# PS_MIO.net
KiCad netlist of a schematic drawn in Altium Designer
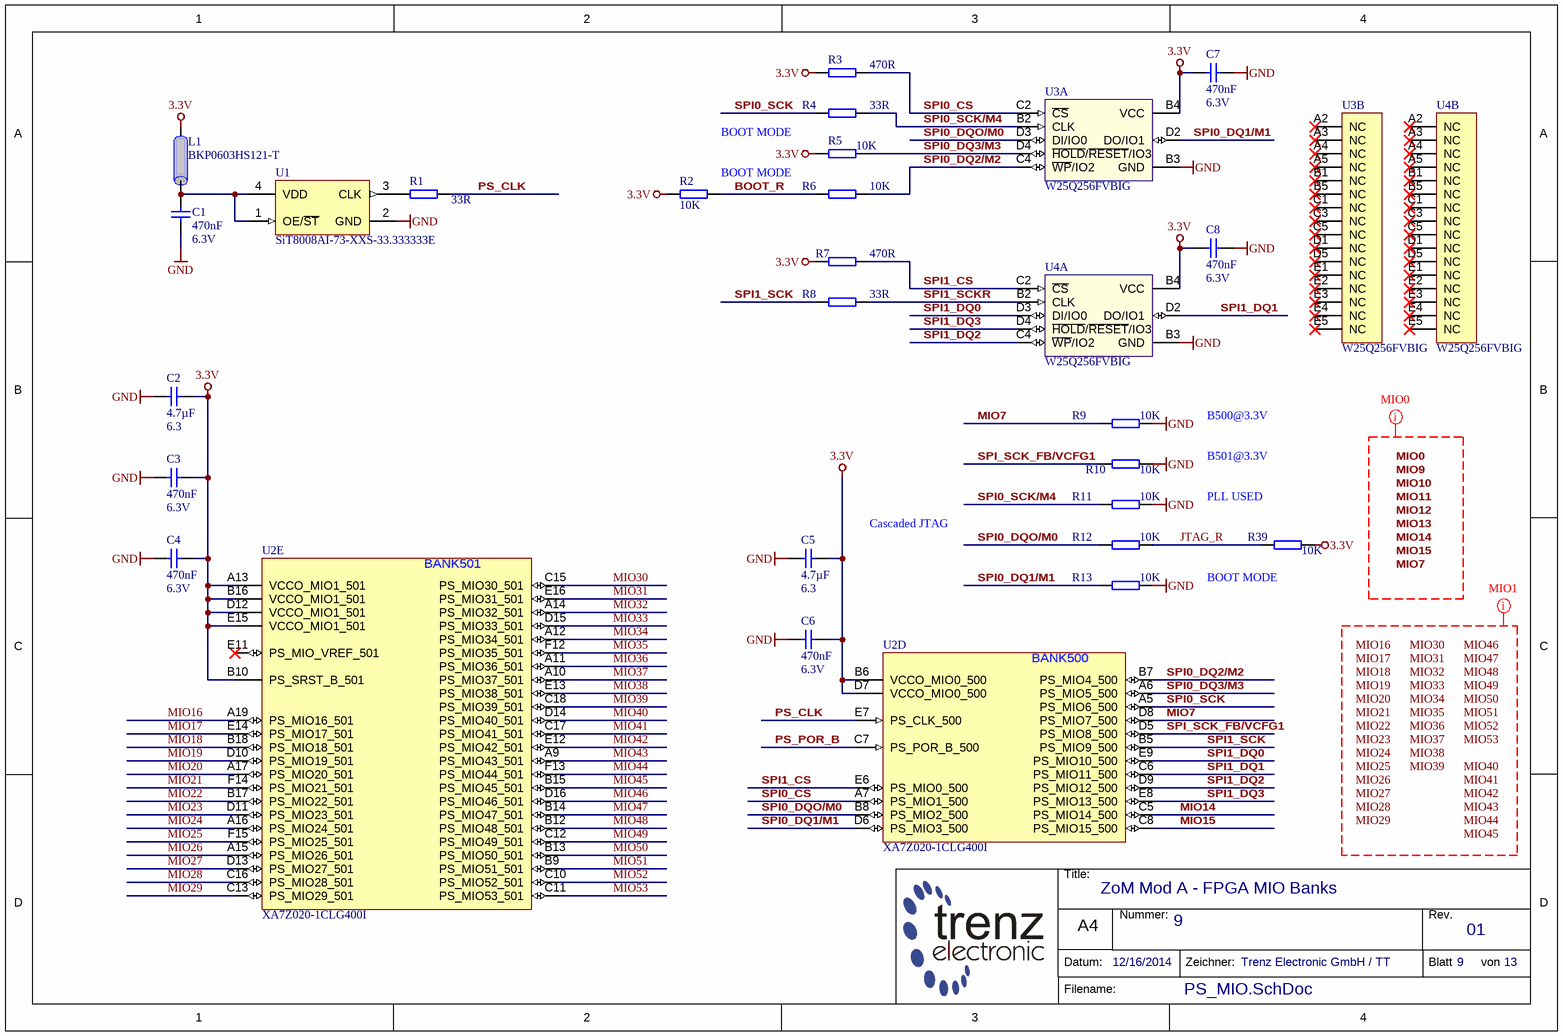
[diagram p0: PS_MIO.SchDoc]

(export (version "E")
  (design (tool "Eeschema 10.0.6"))
  (components
    (comp (ref "C1")
      (value "470nF")
      (footprint "CAPC0603X33N")
      (description "KON 470nF X5R 6.3V SMD")
      (fields (field (name "VOLTAGE") "6.3V") (field (name "TOLERANCE") "20%"))
      (libsource (lib "TE") (part "CAP-NP"))
    )
    (comp (ref "C2")
      (value "4.7µF")
      (footprint "CAPC1005X60N")
      (description "KON 4.7µF 6.3V X5R SMD")
      (fields (field (name "VOLTAGE") "6.3"))
      (libsource (lib "TE") (part "CAP-NP"))
    )
    (comp (ref "C3")
      (value "470nF")
      (footprint "CAPC0603X33N")
      (description "KON 470nF X5R 6.3V SMD")
      (fields (field (name "VOLTAGE") "6.3V") (field (name "TOLERANCE") "20%"))
      (libsource (lib "TE") (part "CAP-NP"))
    )
    (comp (ref "C4")
      (value "470nF")
      (footprint "CAPC0603X33N")
      (description "KON 470nF X5R 6.3V SMD")
      (fields (field (name "VOLTAGE") "6.3V") (field (name "TOLERANCE") "20%"))
      (libsource (lib "TE") (part "CAP-NP"))
    )
    (comp (ref "C5")
      (value "4.7µF")
      (footprint "CAPC1005X60N")
      (description "KON 4.7µF 6.3V X5R SMD")
      (fields (field (name "VOLTAGE") "6.3"))
      (libsource (lib "TE") (part "CAP-NP"))
    )
    (comp (ref "C6")
      (value "470nF")
      (footprint "CAPC0603X33N")
      (description "KON 470nF X5R 6.3V SMD")
      (fields (field (name "VOLTAGE") "6.3V") (field (name "TOLERANCE") "20%"))
      (libsource (lib "TE") (part "CAP-NP"))
    )
    (comp (ref "C7")
      (value "470nF")
      (footprint "CAPC0603X33N")
      (description "KON 470nF X5R 6.3V SMD")
      (fields (field (name "VOLTAGE") "6.3V") (field (name "TOLERANCE") "20%"))
      (libsource (lib "TE") (part "CAP-NP"))
    )
    (comp (ref "C8")
      (value "470nF")
      (footprint "CAPC0603X33N")
      (description "KON 470nF X5R 6.3V SMD")
      (fields (field (name "VOLTAGE") "6.3V") (field (name "TOLERANCE") "20%"))
      (libsource (lib "TE") (part "CAP-NP"))
    )
    (comp (ref "L1")
      (value "BKP0603HS121-T")
      (footprint "INDC0603X33N")
      (description "Ferritdurchführung SMD 0201")
      (libsource (lib "TE") (part "Ferritperle"))
    )
    (comp (ref "R1")
      (value "33R")
      (footprint "RESC0603X26N")
      (description "WID SMD 33R 1% 0,05W")
      (libsource (lib "TE") (part "RES"))
    )
    (comp (ref "R2")
      (value "10K")
      (footprint "RESC0603X26N")
      (description "WID SMD 10K 1% 0,05W")
      (fields (field (name "TOLERANCE") "1%"))
      (libsource (lib "TE") (part "RES"))
    )
    (comp (ref "R3")
      (value "470R")
      (footprint "RESC1005X40N")
      (description "WID SMD 470R 1% 0,063W")
      (fields (field (name "TOLERANCE") "1%"))
      (libsource (lib "TE") (part "RES"))
    )
    (comp (ref "R4")
      (value "33R")
      (footprint "RESC0603X26N")
      (description "WID SMD 33R 1% 0,05W")
      (libsource (lib "TE") (part "RES"))
    )
    (comp (ref "R5")
      (value "10K")
      (footprint "RESC0603X26N")
      (description "WID SMD 10K 1% 0,05W")
      (fields (field (name "TOLERANCE") "1%"))
      (libsource (lib "TE") (part "RES"))
    )
    (comp (ref "R6")
      (value "10K")
      (footprint "RESC0603X26N")
      (description "WID SMD 10K 1% 0,05W")
      (fields (field (name "TOLERANCE") "1%"))
      (libsource (lib "TE") (part "RES"))
    )
    (comp (ref "R7")
      (value "470R")
      (footprint "RESC1005X40N")
      (description "WID SMD 470R 1% 0,063W")
      (fields (field (name "TOLERANCE") "1%"))
      (libsource (lib "TE") (part "RES"))
    )
    (comp (ref "R8")
      (value "33R")
      (footprint "RESC0603X26N")
      (description "WID SMD 33R 1% 0,05W")
      (libsource (lib "TE") (part "RES"))
    )
    (comp (ref "R9")
      (value "10K")
      (footprint "RESC0603X26N")
      (description "WID SMD 10K 1% 0,05W")
      (fields (field (name "TOLERANCE") "1%"))
      (libsource (lib "TE") (part "RES"))
    )
    (comp (ref "R10")
      (value "10K")
      (footprint "RESC0603X26N")
      (description "WID SMD 10K 1% 0,05W")
      (fields (field (name "TOLERANCE") "1%"))
      (libsource (lib "TE") (part "RES"))
    )
    (comp (ref "R11")
      (value "10K")
      (footprint "RESC0603X26N")
      (description "WID SMD 10K 1% 0,05W")
      (fields (field (name "TOLERANCE") "1%"))
      (libsource (lib "TE") (part "RES"))
    )
    (comp (ref "R12")
      (value "10K")
      (footprint "RESC0603X26N")
      (description "WID SMD 10K 1% 0,05W")
      (fields (field (name "TOLERANCE") "1%"))
      (libsource (lib "TE") (part "RES"))
    )
    (comp (ref "R13")
      (value "10K")
      (footprint "RESC0603X26N")
      (description "WID SMD 10K 1% 0,05W")
      (fields (field (name "TOLERANCE") "1%"))
      (libsource (lib "TE") (part "RES"))
    )
    (comp (ref "R39")
      (value "10K")
      (footprint "RESC0603X26N")
      (description "WID SMD 10K 1% 0,05W")
      (fields (field (name "TOLERANCE") "1%"))
      (libsource (lib "TE") (part "RES"))
    )
    (comp (ref "U1")
      (value "SiT8008AI-73-XXS-33.333333E")
      (footprint "2016")
      (description "SiT8008AI-73-XXS-33.333333E MEMS Oszillator 33.333333MHz")
      (libsource (lib "TE") (part "SiT8103"))
    )
    (comp (ref "U2")
      (value "XA7Z020-1CLG400I")
      (footprint "BGA400C80P20X20_1700X1700X160N")
      (libsource (lib "TE") (part "XC7Z020-2CLG400C"))
    )
    (comp (ref "U3")
      (value "W25Q256FVBIG")
      (footprint "BGA24C100P5X5_800X600X120N")
      (libsource (lib "TE") (part "W25Q256FVBIG"))
    )
    (comp (ref "U4")
      (value "W25Q256FVBIG")
      (footprint "BGA24C100P5X5_800X600X120N")
      (libsource (lib "TE") (part "W25Q256FVBIG"))
    )
  )
  (nets
    (net (code "1") (name "/BOOT_R") (class "Default")
      (node (ref "R2") (pin "1") (pinfunction "1_1") (pintype "passive"))
      (node (ref "R6") (pin "2") (pinfunction "2_2") (pintype "passive"))
    )
    (net (code "2") (name "/JTAG_R") (class "Default")
      (node (ref "R12") (pin "1") (pinfunction "1_1") (pintype "passive"))
      (node (ref "R39") (pin "2") (pinfunction "2_2") (pintype "passive"))
    )
    (net (code "4") (name "/MIO7") (class "Default")
      (node (ref "R9") (pin "2") (pinfunction "2_2") (pintype "passive"))
      (node (ref "U2") (pin "D8") (pinfunction "PS_MIO7_500_D8") (pintype "bidirectional"))
    )
    (net (code "10") (name "/MIO14") (class "Default")
      (node (ref "U2") (pin "C5") (pinfunction "PS_MIO14_500_C5") (pintype "bidirectional"))
    )
    (net (code "11") (name "/MIO15") (class "Default")
      (node (ref "U2") (pin "C8") (pinfunction "PS_MIO15_500_C8") (pintype "bidirectional"))
    )
    (net (code "12") (name "/MIO16") (class "Default")
      (node (ref "U2") (pin "A19") (pinfunction "PS_MIO16_501_A19") (pintype "bidirectional"))
    )
    (net (code "13") (name "/MIO17") (class "Default")
      (node (ref "U2") (pin "E14") (pinfunction "PS_MIO17_501_E14") (pintype "bidirectional"))
    )
    (net (code "14") (name "/MIO18") (class "Default")
      (node (ref "U2") (pin "B18") (pinfunction "PS_MIO18_501_B18") (pintype "bidirectional"))
    )
    (net (code "15") (name "/MIO19") (class "Default")
      (node (ref "U2") (pin "D10") (pinfunction "PS_MIO19_501_D10") (pintype "bidirectional"))
    )
    (net (code "16") (name "/MIO20") (class "Default")
      (node (ref "U2") (pin "A17") (pinfunction "PS_MIO20_501_A17") (pintype "bidirectional"))
    )
    (net (code "17") (name "/MIO21") (class "Default")
      (node (ref "U2") (pin "F14") (pinfunction "PS_MIO21_501_F14") (pintype "bidirectional"))
    )
    (net (code "18") (name "/MIO22") (class "Default")
      (node (ref "U2") (pin "B17") (pinfunction "PS_MIO22_501_B17") (pintype "bidirectional"))
    )
    (net (code "19") (name "/MIO23") (class "Default")
      (node (ref "U2") (pin "D11") (pinfunction "PS_MIO23_501_D11") (pintype "bidirectional"))
    )
    (net (code "20") (name "/MIO24") (class "Default")
      (node (ref "U2") (pin "A16") (pinfunction "PS_MIO24_501_A16") (pintype "bidirectional"))
    )
    (net (code "21") (name "/MIO25") (class "Default")
      (node (ref "U2") (pin "F15") (pinfunction "PS_MIO25_501_F15") (pintype "bidirectional"))
    )
    (net (code "22") (name "/MIO26") (class "Default")
      (node (ref "U2") (pin "A15") (pinfunction "PS_MIO26_501_A15") (pintype "bidirectional"))
    )
    (net (code "23") (name "/MIO27") (class "Default")
      (node (ref "U2") (pin "D13") (pinfunction "PS_MIO27_501_D13") (pintype "bidirectional"))
    )
    (net (code "24") (name "/MIO28") (class "Default")
      (node (ref "U2") (pin "C16") (pinfunction "PS_MIO28_501_C16") (pintype "bidirectional"))
    )
    (net (code "25") (name "/MIO29") (class "Default")
      (node (ref "U2") (pin "C13") (pinfunction "PS_MIO29_501_C13") (pintype "bidirectional"))
    )
    (net (code "26") (name "/MIO30") (class "Default")
      (node (ref "U2") (pin "C15") (pinfunction "PS_MIO30_501_C15") (pintype "bidirectional"))
    )
    (net (code "27") (name "/MIO31") (class "Default")
      (node (ref "U2") (pin "E16") (pinfunction "PS_MIO31_501_E16") (pintype "bidirectional"))
    )
    (net (code "28") (name "/MIO32") (class "Default")
      (node (ref "U2") (pin "A14") (pinfunction "PS_MIO32_501_A14") (pintype "bidirectional"))
    )
    (net (code "29") (name "/MIO33") (class "Default")
      (node (ref "U2") (pin "D15") (pinfunction "PS_MIO33_501_D15") (pintype "bidirectional"))
    )
    (net (code "30") (name "/MIO34") (class "Default")
      (node (ref "U2") (pin "A12") (pinfunction "PS_MIO34_501_A12") (pintype "bidirectional"))
    )
    (net (code "31") (name "/MIO35") (class "Default")
      (node (ref "U2") (pin "F12") (pinfunction "PS_MIO35_501_F12") (pintype "bidirectional"))
    )
    (net (code "32") (name "/MIO36") (class "Default")
      (node (ref "U2") (pin "A11") (pinfunction "PS_MIO36_501_A11") (pintype "bidirectional"))
    )
    (net (code "33") (name "/MIO37") (class "Default")
      (node (ref "U2") (pin "A10") (pinfunction "PS_MIO37_501_A10") (pintype "bidirectional"))
    )
    (net (code "34") (name "/MIO38") (class "Default")
      (node (ref "U2") (pin "E13") (pinfunction "PS_MIO38_501_E13") (pintype "bidirectional"))
    )
    (net (code "35") (name "/MIO39") (class "Default")
      (node (ref "U2") (pin "C18") (pinfunction "PS_MIO39_501_C18") (pintype "bidirectional"))
    )
    (net (code "36") (name "/MIO40") (class "Default")
      (node (ref "U2") (pin "D14") (pinfunction "PS_MIO40_501_D14") (pintype "bidirectional"))
    )
    (net (code "37") (name "/MIO41") (class "Default")
      (node (ref "U2") (pin "C17") (pinfunction "PS_MIO41_501_C17") (pintype "bidirectional"))
    )
    (net (code "38") (name "/MIO42") (class "Default")
      (node (ref "U2") (pin "E12") (pinfunction "PS_MIO42_501_E12") (pintype "bidirectional"))
    )
    (net (code "39") (name "/MIO43") (class "Default")
      (node (ref "U2") (pin "A9") (pinfunction "PS_MIO43_501_A9") (pintype "bidirectional"))
    )
    (net (code "40") (name "/MIO44") (class "Default")
      (node (ref "U2") (pin "F13") (pinfunction "PS_MIO44_501_F13") (pintype "bidirectional"))
    )
    (net (code "41") (name "/MIO45") (class "Default")
      (node (ref "U2") (pin "B15") (pinfunction "PS_MIO45_501_B15") (pintype "bidirectional"))
    )
    (net (code "42") (name "/MIO46") (class "Default")
      (node (ref "U2") (pin "D16") (pinfunction "PS_MIO46_501_D16") (pintype "bidirectional"))
    )
    (net (code "43") (name "/MIO47") (class "Default")
      (node (ref "U2") (pin "B14") (pinfunction "PS_MIO47_501_B14") (pintype "bidirectional"))
    )
    (net (code "44") (name "/MIO48") (class "Default")
      (node (ref "U2") (pin "B12") (pinfunction "PS_MIO48_501_B12") (pintype "bidirectional"))
    )
    (net (code "45") (name "/MIO49") (class "Default")
      (node (ref "U2") (pin "C12") (pinfunction "PS_MIO49_501_C12") (pintype "bidirectional"))
    )
    (net (code "46") (name "/MIO50") (class "Default")
      (node (ref "U2") (pin "B13") (pinfunction "PS_MIO50_501_B13") (pintype "bidirectional"))
    )
    (net (code "47") (name "/MIO51") (class "Default")
      (node (ref "U2") (pin "B9") (pinfunction "PS_MIO51_501_B9") (pintype "bidirectional"))
    )
    (net (code "48") (name "/MIO52") (class "Default")
      (node (ref "U2") (pin "C10") (pinfunction "PS_MIO52_501_C10") (pintype "bidirectional"))
    )
    (net (code "49") (name "/MIO53") (class "Default")
      (node (ref "U2") (pin "C11") (pinfunction "PS_MIO53_501_C11") (pintype "bidirectional"))
    )
    (net (code "50") (name "/PS_CLK") (class "Default")
      (node (ref "R1") (pin "2") (pinfunction "2_2") (pintype "passive"))
      (node (ref "U2") (pin "E7") (pinfunction "PS_CLK_500_E7") (pintype "input"))
    )
    (net (code "51") (name "/PS_POR_B") (class "Default")
      (node (ref "U2") (pin "C7") (pinfunction "PS_POR_B_500_C7") (pintype "input"))
    )
    (net (code "52") (name "/SPI0_CS") (class "Default")
      (node (ref "R3") (pin "2") (pinfunction "2_2") (pintype "passive"))
      (node (ref "U2") (pin "A7") (pinfunction "PS_MIO1_500_A7") (pintype "bidirectional"))
      (node (ref "U3") (pin "C2") (pinfunction "~{CS}_C2") (pintype "input"))
    )
    (net (code "53") (name "/SPI0_DQ1{slash}M1") (class "Default")
      (node (ref "R13") (pin "2") (pinfunction "2_2") (pintype "passive"))
      (node (ref "U2") (pin "D6") (pinfunction "PS_MIO3_500_D6") (pintype "bidirectional"))
      (node (ref "U3") (pin "D2") (pinfunction "DO/IO1_D2") (pintype "bidirectional"))
    )
    (net (code "54") (name "/SPI0_DQ2{slash}M2") (class "Default")
      (node (ref "R6") (pin "1") (pinfunction "1_1") (pintype "passive"))
      (node (ref "U2") (pin "B7") (pinfunction "PS_MIO4_500_B7") (pintype "bidirectional"))
      (node (ref "U3") (pin "C4") (pinfunction "~{WP}/IO2_C4") (pintype "bidirectional"))
    )
    (net (code "55") (name "/SPI0_DQ3{slash}M3") (class "Default")
      (node (ref "R5") (pin "1") (pinfunction "1_1") (pintype "passive"))
      (node (ref "U2") (pin "A6") (pinfunction "PS_MIO5_500_A6") (pintype "bidirectional"))
      (node (ref "U3") (pin "D4") (pinfunction "~{HOLD}/~{RESET}/IO3_D4") (pintype "bidirectional"))
    )
    (net (code "56") (name "/SPI0_DQO{slash}M0") (class "Default")
      (node (ref "R12") (pin "2") (pinfunction "2_2") (pintype "passive"))
      (node (ref "U2") (pin "B8") (pinfunction "PS_MIO2_500_B8") (pintype "bidirectional"))
      (node (ref "U3") (pin "D3") (pinfunction "DI/IO0_D3") (pintype "bidirectional"))
    )
    (net (code "57") (name "/SPI0_SCK") (class "Default")
      (node (ref "R4") (pin "1") (pinfunction "1_1") (pintype "passive"))
      (node (ref "U2") (pin "A5") (pinfunction "PS_MIO6_500_A5") (pintype "bidirectional"))
    )
    (net (code "58") (name "/SPI0_SCK{slash}M4") (class "Default")
      (node (ref "R11") (pin "2") (pinfunction "2_2") (pintype "passive"))
      (node (ref "R4") (pin "2") (pinfunction "2_2") (pintype "passive"))
      (node (ref "U3") (pin "B2") (pinfunction "CLK_B2") (pintype "input"))
    )
    (net (code "59") (name "/SPI1_CS") (class "Default")
      (node (ref "R7") (pin "1") (pinfunction "1_1") (pintype "passive"))
      (node (ref "U2") (pin "E6") (pinfunction "PS_MIO0_500_E6") (pintype "bidirectional"))
      (node (ref "U4") (pin "C2") (pinfunction "~{CS}_C2") (pintype "input"))
    )
    (net (code "60") (name "/SPI1_DQ0") (class "Default")
      (node (ref "U2") (pin "E9") (pinfunction "PS_MIO10_500_E9") (pintype "bidirectional"))
      (node (ref "U4") (pin "D3") (pinfunction "DI/IO0_D3") (pintype "bidirectional"))
    )
    (net (code "61") (name "/SPI1_DQ1") (class "Default")
      (node (ref "U2") (pin "C6") (pinfunction "PS_MIO11_500_C6") (pintype "bidirectional"))
      (node (ref "U4") (pin "D2") (pinfunction "DO/IO1_D2") (pintype "bidirectional"))
    )
    (net (code "62") (name "/SPI1_DQ2") (class "Default")
      (node (ref "U2") (pin "D9") (pinfunction "PS_MIO12_500_D9") (pintype "bidirectional"))
      (node (ref "U4") (pin "C4") (pinfunction "~{WP}/IO2_C4") (pintype "bidirectional"))
    )
    (net (code "63") (name "/SPI1_DQ3") (class "Default")
      (node (ref "U2") (pin "E8") (pinfunction "PS_MIO13_500_E8") (pintype "bidirectional"))
      (node (ref "U4") (pin "D4") (pinfunction "~{HOLD}/~{RESET}/IO3_D4") (pintype "bidirectional"))
    )
    (net (code "64") (name "/SPI1_SCK") (class "Default")
      (node (ref "R8") (pin "1") (pinfunction "1_1") (pintype "passive"))
      (node (ref "U2") (pin "B5") (pinfunction "PS_MIO9_500_B5") (pintype "bidirectional"))
    )
    (net (code "65") (name "/SPI1_SCKR") (class "Default")
      (node (ref "R8") (pin "2") (pinfunction "2_2") (pintype "passive"))
      (node (ref "U4") (pin "B2") (pinfunction "CLK_B2") (pintype "input"))
    )
    (net (code "66") (name "/SPI_SCK_FB{slash}VCFG1") (class "Default")
      (node (ref "R10") (pin "2") (pinfunction "2_2") (pintype "passive"))
      (node (ref "U2") (pin "D5") (pinfunction "PS_MIO8_500_D5") (pintype "bidirectional"))
    )
    (net (code "67") (name "3.3V") (class "Default")
      (node (ref "C2") (pin "1") (pinfunction "1_1") (pintype "passive"))
      (node (ref "C3") (pin "1") (pinfunction "1_1") (pintype "passive"))
      (node (ref "C4") (pin "1") (pinfunction "1_1") (pintype "passive"))
      (node (ref "C5") (pin "1") (pinfunction "1_1") (pintype "passive"))
      (node (ref "C6") (pin "1") (pinfunction "1_1") (pintype "passive"))
      (node (ref "C7") (pin "1") (pinfunction "1_1") (pintype "passive"))
      (node (ref "C8") (pin "1") (pinfunction "1_1") (pintype "passive"))
      (node (ref "L1") (pin "1") (pinfunction "1_1") (pintype "passive"))
      (node (ref "R2") (pin "2") (pinfunction "2_2") (pintype "passive"))
      (node (ref "R3") (pin "1") (pinfunction "1_1") (pintype "passive"))
      (node (ref "R39") (pin "1") (pinfunction "1_1") (pintype "passive"))
      (node (ref "R5") (pin "2") (pinfunction "2_2") (pintype "passive"))
      (node (ref "R7") (pin "2") (pinfunction "2_2") (pintype "passive"))
      (node (ref "U2") (pin "A13") (pinfunction "VCCO_MIO1_501_A13") (pintype "power_in"))
      (node (ref "U2") (pin "B10") (pinfunction "PS_SRST_B_501_B10") (pintype "passive"))
      (node (ref "U2") (pin "B16") (pinfunction "VCCO_MIO1_501_B16") (pintype "power_in"))
      (node (ref "U2") (pin "B6") (pinfunction "VCCO_MIO0_500_B6") (pintype "power_in"))
      (node (ref "U2") (pin "D12") (pinfunction "VCCO_MIO1_501_D12") (pintype "power_in"))
      (node (ref "U2") (pin "D7") (pinfunction "VCCO_MIO0_500_D7") (pintype "power_in"))
      (node (ref "U2") (pin "E15") (pinfunction "VCCO_MIO1_501_E15") (pintype "power_in"))
      (node (ref "U3") (pin "B4") (pinfunction "VCC_B4") (pintype "power_in"))
      (node (ref "U4") (pin "B4") (pinfunction "VCC_B4") (pintype "power_in"))
    )
    (net (code "68") (name "GND") (class "Default")
      (node (ref "C1") (pin "2") (pinfunction "2_2") (pintype "passive"))
      (node (ref "C2") (pin "2") (pinfunction "2_2") (pintype "passive"))
      (node (ref "C3") (pin "2") (pinfunction "2_2") (pintype "passive"))
      (node (ref "C4") (pin "2") (pinfunction "2_2") (pintype "passive"))
      (node (ref "C5") (pin "2") (pinfunction "2_2") (pintype "passive"))
      (node (ref "C6") (pin "2") (pinfunction "2_2") (pintype "passive"))
      (node (ref "C7") (pin "2") (pinfunction "2_2") (pintype "passive"))
      (node (ref "C8") (pin "2") (pinfunction "2_2") (pintype "passive"))
      (node (ref "R10") (pin "1") (pinfunction "1_1") (pintype "passive"))
      (node (ref "R11") (pin "1") (pinfunction "1_1") (pintype "passive"))
      (node (ref "R13") (pin "1") (pinfunction "1_1") (pintype "passive"))
      (node (ref "R9") (pin "1") (pinfunction "1_1") (pintype "passive"))
      (node (ref "U1") (pin "2") (pinfunction "GND_2") (pintype "power_in"))
      (node (ref "U3") (pin "B3") (pinfunction "GND_B3") (pintype "power_in"))
      (node (ref "U4") (pin "B3") (pinfunction "GND_B3") (pintype "power_in"))
    )
    (net (code "69") (name "Net-(U1-CLK)") (class "Default")
      (node (ref "R1") (pin "1") (pinfunction "1_1") (pintype "passive"))
      (node (ref "U1") (pin "3") (pinfunction "CLK_3") (pintype "output"))
    )
    (net (code "70") (name "Net-(U1-OE{slash}~{ST})") (class "Default")
      (node (ref "C1") (pin "1") (pinfunction "1_1") (pintype "passive"))
      (node (ref "L1") (pin "2") (pinfunction "2_2") (pintype "passive"))
      (node (ref "U1") (pin "1") (pinfunction "OE/~{ST}_1") (pintype "input"))
      (node (ref "U1") (pin "4") (pinfunction "VDD_4") (pintype "power_in"))
    )
    (net (code "71") (name "unconnected-(U2E-PS_MIO_VREF_501-PadE11)") (class "Default")
      (node (ref "U2") (pin "E11") (pinfunction "PS_MIO_VREF_501_E11") (pintype "bidirectional+no_connect"))
    )
    (net (code "72") (name "unconnected-(U3B-NC-PadA2)") (class "Default")
      (node (ref "U3") (pin "A2") (pinfunction "NC_A2") (pintype "passive+no_connect"))
    )
    (net (code "73") (name "unconnected-(U3B-NC-PadA3)") (class "Default")
      (node (ref "U3") (pin "A3") (pinfunction "NC_A3") (pintype "passive+no_connect"))
    )
    (net (code "74") (name "unconnected-(U3B-NC-PadA4)") (class "Default")
      (node (ref "U3") (pin "A4") (pinfunction "NC_A4") (pintype "passive+no_connect"))
    )
    (net (code "75") (name "unconnected-(U3B-NC-PadA5)") (class "Default")
      (node (ref "U3") (pin "A5") (pinfunction "NC_A5") (pintype "passive+no_connect"))
    )
    (net (code "76") (name "unconnected-(U3B-NC-PadB1)") (class "Default")
      (node (ref "U3") (pin "B1") (pinfunction "NC_B1") (pintype "passive+no_connect"))
    )
    (net (code "77") (name "unconnected-(U3B-NC-PadB5)") (class "Default")
      (node (ref "U3") (pin "B5") (pinfunction "NC_B5") (pintype "passive+no_connect"))
    )
    (net (code "78") (name "unconnected-(U3B-NC-PadC1)") (class "Default")
      (node (ref "U3") (pin "C1") (pinfunction "NC_C1") (pintype "passive+no_connect"))
    )
    (net (code "79") (name "unconnected-(U3B-NC-PadC3)") (class "Default")
      (node (ref "U3") (pin "C3") (pinfunction "NC_C3") (pintype "passive+no_connect"))
    )
    (net (code "80") (name "unconnected-(U3B-NC-PadC5)") (class "Default")
      (node (ref "U3") (pin "C5") (pinfunction "NC_C5") (pintype "passive+no_connect"))
    )
    (net (code "81") (name "unconnected-(U3B-NC-PadD1)") (class "Default")
      (node (ref "U3") (pin "D1") (pinfunction "NC_D1") (pintype "passive+no_connect"))
    )
    (net (code "82") (name "unconnected-(U3B-NC-PadD5)") (class "Default")
      (node (ref "U3") (pin "D5") (pinfunction "NC_D5") (pintype "passive+no_connect"))
    )
    (net (code "83") (name "unconnected-(U3B-NC-PadE1)") (class "Default")
      (node (ref "U3") (pin "E1") (pinfunction "NC_E1") (pintype "passive+no_connect"))
    )
    (net (code "84") (name "unconnected-(U3B-NC-PadE2)") (class "Default")
      (node (ref "U3") (pin "E2") (pinfunction "NC_E2") (pintype "passive+no_connect"))
    )
    (net (code "85") (name "unconnected-(U3B-NC-PadE3)") (class "Default")
      (node (ref "U3") (pin "E3") (pinfunction "NC_E3") (pintype "passive+no_connect"))
    )
    (net (code "86") (name "unconnected-(U3B-NC-PadE4)") (class "Default")
      (node (ref "U3") (pin "E4") (pinfunction "NC_E4") (pintype "passive+no_connect"))
    )
    (net (code "87") (name "unconnected-(U3B-NC-PadE5)") (class "Default")
      (node (ref "U3") (pin "E5") (pinfunction "NC_E5") (pintype "passive+no_connect"))
    )
    (net (code "88") (name "unconnected-(U4B-NC-PadA2)") (class "Default")
      (node (ref "U4") (pin "A2") (pinfunction "NC_A2") (pintype "passive+no_connect"))
    )
    (net (code "89") (name "unconnected-(U4B-NC-PadA3)") (class "Default")
      (node (ref "U4") (pin "A3") (pinfunction "NC_A3") (pintype "passive+no_connect"))
    )
    (net (code "90") (name "unconnected-(U4B-NC-PadA4)") (class "Default")
      (node (ref "U4") (pin "A4") (pinfunction "NC_A4") (pintype "passive+no_connect"))
    )
    (net (code "91") (name "unconnected-(U4B-NC-PadA5)") (class "Default")
      (node (ref "U4") (pin "A5") (pinfunction "NC_A5") (pintype "passive+no_connect"))
    )
    (net (code "92") (name "unconnected-(U4B-NC-PadB1)") (class "Default")
      (node (ref "U4") (pin "B1") (pinfunction "NC_B1") (pintype "passive+no_connect"))
    )
    (net (code "93") (name "unconnected-(U4B-NC-PadB5)") (class "Default")
      (node (ref "U4") (pin "B5") (pinfunction "NC_B5") (pintype "passive+no_connect"))
    )
    (net (code "94") (name "unconnected-(U4B-NC-PadC1)") (class "Default")
      (node (ref "U4") (pin "C1") (pinfunction "NC_C1") (pintype "passive+no_connect"))
    )
    (net (code "95") (name "unconnected-(U4B-NC-PadC3)") (class "Default")
      (node (ref "U4") (pin "C3") (pinfunction "NC_C3") (pintype "passive+no_connect"))
    )
    (net (code "96") (name "unconnected-(U4B-NC-PadC5)") (class "Default")
      (node (ref "U4") (pin "C5") (pinfunction "NC_C5") (pintype "passive+no_connect"))
    )
    (net (code "97") (name "unconnected-(U4B-NC-PadD1)") (class "Default")
      (node (ref "U4") (pin "D1") (pinfunction "NC_D1") (pintype "passive+no_connect"))
    )
    (net (code "98") (name "unconnected-(U4B-NC-PadD5)") (class "Default")
      (node (ref "U4") (pin "D5") (pinfunction "NC_D5") (pintype "passive+no_connect"))
    )
    (net (code "99") (name "unconnected-(U4B-NC-PadE1)") (class "Default")
      (node (ref "U4") (pin "E1") (pinfunction "NC_E1") (pintype "passive+no_connect"))
    )
    (net (code "100") (name "unconnected-(U4B-NC-PadE2)") (class "Default")
      (node (ref "U4") (pin "E2") (pinfunction "NC_E2") (pintype "passive+no_connect"))
    )
    (net (code "101") (name "unconnected-(U4B-NC-PadE3)") (class "Default")
      (node (ref "U4") (pin "E3") (pinfunction "NC_E3") (pintype "passive+no_connect"))
    )
    (net (code "102") (name "unconnected-(U4B-NC-PadE4)") (class "Default")
      (node (ref "U4") (pin "E4") (pinfunction "NC_E4") (pintype "passive+no_connect"))
    )
    (net (code "103") (name "unconnected-(U4B-NC-PadE5)") (class "Default")
      (node (ref "U4") (pin "E5") (pinfunction "NC_E5") (pintype "passive+no_connect"))
    )
  )
)
